# Sheet2.net
KiCad netlist of a schematic drawn in Altium Designer
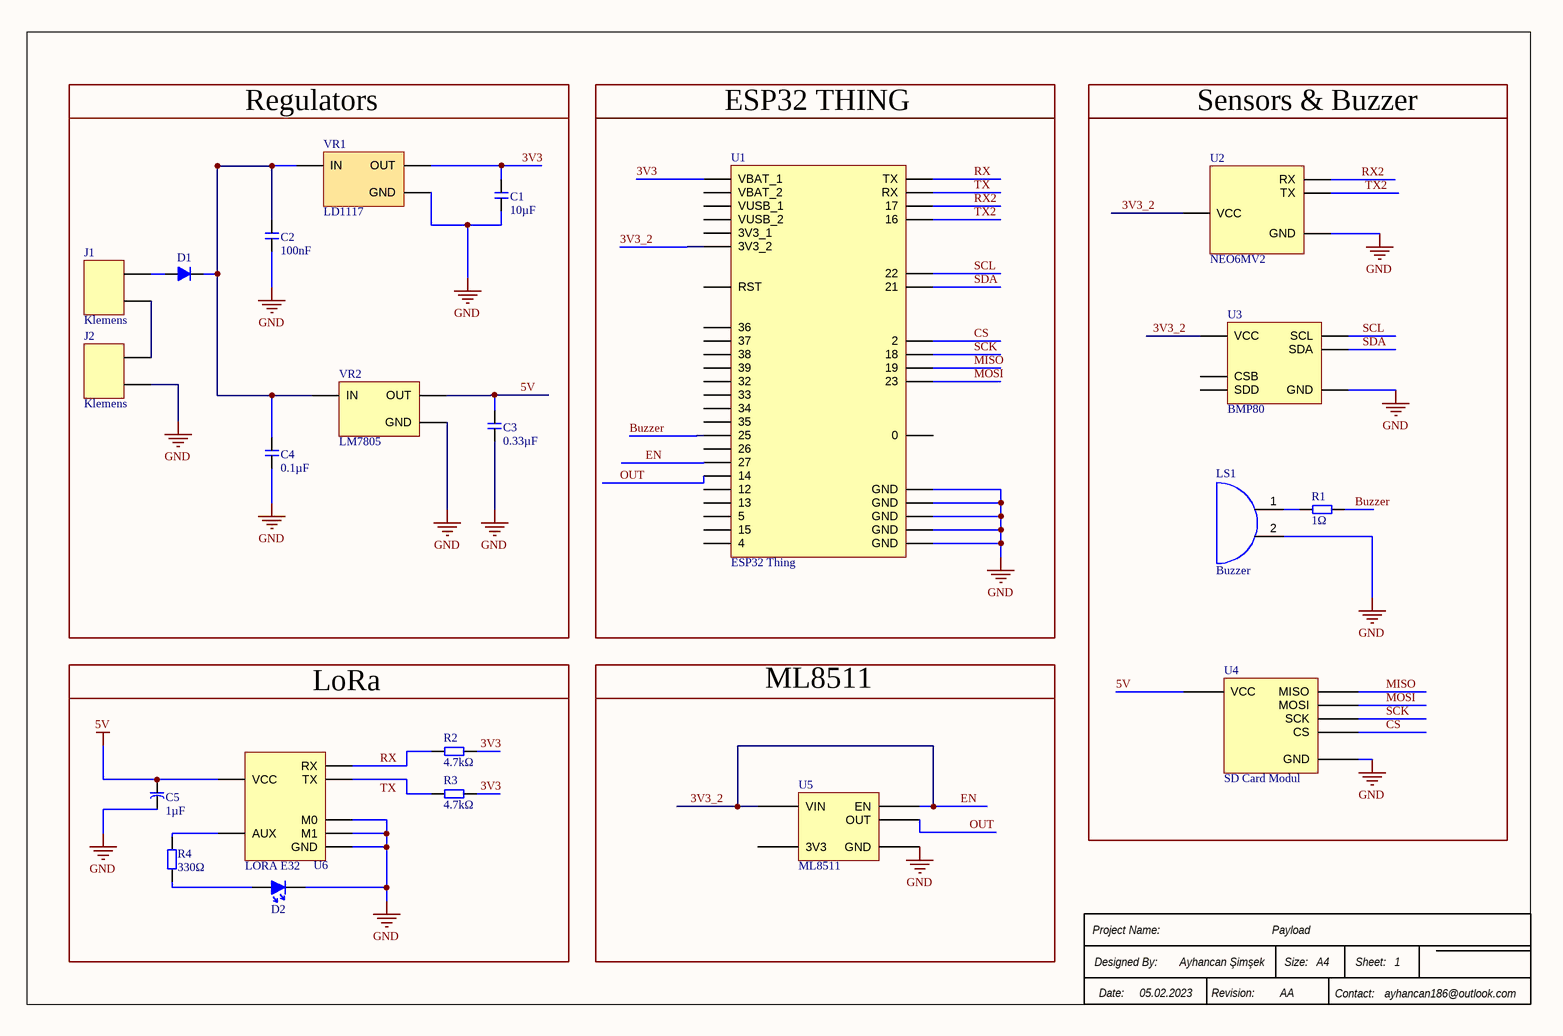
[diagram p0: Sheet2.SchDoc]

(export (version "E")
  (design (tool "Eeschema 10.0.6"))
  (components
    (comp (ref "C1") (value "10µF") (footprint "LCapacitor") (libsource (lib "Schlib1") (part "Capacitor")))
    (comp (ref "C2") (value "100nF") (footprint "LCapacitor") (libsource (lib "Schlib1") (part "Capacitor")))
    (comp (ref "C3") (value "0.33µF") (footprint "LCapacitor") (libsource (lib "Schlib1") (part "Capacitor")))
    (comp (ref "C4") (value "0.1µF") (footprint "LCapacitor") (libsource (lib "Schlib1") (part "Capacitor")))
    (comp (ref "C5") (value "1µF") (footprint "Capacitor") (libsource (lib "Schlib1") (part "DCapacitor")))
    (comp (ref "D1")
      (value "Diode")
      (footprint "Zener")
      (libsource (lib "Integrated_Library2") (part "Diode"))
    )
    (comp (ref "D2") (value "Led") (footprint "LED") (libsource (lib "Integrated_Library2") (part "Led")))
    (comp (ref "J1")
      (value "Klemens")
      (footprint "Klemens")
      (libsource (lib "Integrated_Library2") (part "Klemens"))
    )
    (comp (ref "J2")
      (value "Klemens")
      (footprint "Klemens")
      (libsource (lib "Integrated_Library2") (part "Klemens"))
    )
    (comp (ref "LS1")
      (value "Buzzer")
      (footprint "Buzzer")
      (libsource (lib "Integrated_Library2") (part "Buzzer"))
    )
    (comp (ref "R1") (value "1Ω") (footprint "Resistor") (libsource (lib "Schlib1") (part "Resistor")))
    (comp (ref "R2") (value "4.7kΩ") (footprint "Resistor") (libsource (lib "Schlib1") (part "Resistor")))
    (comp (ref "R3") (value "4.7kΩ") (footprint "Resistor") (libsource (lib "Schlib1") (part "Resistor")))
    (comp (ref "R4") (value "330Ω") (footprint "Resistor") (libsource (lib "Schlib1") (part "Resistor")))
    (comp (ref "U1")
      (value "ESP32 Thing")
      (footprint "ESP32 THING")
      (description "ESP32 802.11 Wireless LAN/Combo Wireless Module Development Kit")
      (fields (field (name "MANUFACTURER") "SparkFun") (field (name "MANUFACTURER PART NUMBER") "DEV-13907"))
      (libsource (lib "Integrated_Library2") (part "ESP32 Thing"))
    )
    (comp (ref "U2")
      (value "NEO6MV2")
      (footprint "NEO6MV2")
      (description "U#NEO-6M Gps Module U-BLOX6 SMD24P")
      (fields (field (name "MANUFACTURER") "u-blox") (field (name "MANUFACTURER PART NUMBER") "NEO-6M-0"))
      (libsource (lib "Integrated_Library2") (part "NEO6MV2"))
    )
    (comp (ref "U3")
      (value "BMP80")
      (footprint "BMP280")
      (description "Washer; #2 Screw Clr; 3/32 ID; 1/4 OD; 1/32 Height; Nylon")
      (fields (field (name "MANUFACTURER") "Bosch") (field (name "MANUFACTURER PART NUMBER") "BMP280"))
      (libsource (lib "Integrated_Library2") (part "BMP80"))
    )
    (comp (ref "U4")
      (value "SD Card Modul")
      (footprint "SD Card Modülü")
      (libsource (lib "Integrated_Library2") (part "SD Card Modul"))
    )
    (comp (ref "U5")
      (value "ML8511")
      (footprint "ML8511")
      (description "IC, Uv Sensor, Voltage Output, QFN-12")
      (fields
        (field (name "MANUFACTURER") "Rohm")
        (field (name "MANUFACTURER PART NUMBER") "ML8511-00FCZ05B")
      )
      (libsource (lib "Integrated_Library2") (part "ML8511"))
    )
    (comp (ref "U6")
      (value "LORA E32")
      (footprint "LORAE32")
      (description "WiFi-Modul 802.11/BT 2, 4-2, 5GHz 150Mb/s")
      (fields
        (field (name "MANUFACTURER") "Espressif Systems")
        (field (name "MANUFACTURER PART NUMBER") "ESP32-S3-WROOM-1-N16R8")
      )
      (libsource (lib "Integrated_Library2") (part "LORA E32"))
    )
    (comp (ref "VR1")
      (value "LD1117")
      (footprint "LD1117")
      (description "LDO Regulator Pos 3.3V 1.3A 3-Pin(3+Tab) TO-220 Tube (Alt: LD1117V33C)")
      (fields
        (field (name "MANUFACTURER") "STMicroelectronics")
        (field (name "MANUFACTURER PART NUMBER") "LD1117V33C")
      )
      (libsource (lib "Integrated_Library2") (part "LD1117"))
    )
    (comp (ref "VR2")
      (value "LM7805")
      (footprint "LM7805")
      (description "LM78XX Series 5 V Fixed Output 1 A 3-Terminal LDO Voltage Regulator - TO-220")
      (fields
        (field (name "MANUFACTURER") "ON Semiconductor / Fairchild")
        (field (name "MANUFACTURER PART NUMBER") "LM7805CT")
      )
      (libsource (lib "Integrated_Library2") (part "LM7805"))
    )
  )
  (nets
    (net (code "1") (name "/3V3") (class "Default")
      (node (ref "C1") (pin "2") (pinfunction "2_2") (pintype "passive"))
      (node (ref "R2") (pin "2") (pinfunction "2_2") (pintype "passive"))
      (node (ref "R3") (pin "2") (pinfunction "2_2") (pintype "passive"))
      (node (ref "U1") (pin "VBAT_1") (pinfunction "VBAT_1_VBAT_1") (pintype "passive"))
      (node (ref "VR1") (pin "2") (pinfunction "OUT_2") (pintype "passive"))
    )
    (net (code "2") (name "/3V3_2") (class "Default")
      (node (ref "U1") (pin "27") (pinfunction "27_27") (pintype "passive"))
      (node (ref "U1") (pin "3V3_2") (pinfunction "3V3_2_3V3_2") (pintype "passive"))
      (node (ref "U2") (pin "1") (pinfunction "VCC_1") (pintype "passive"))
      (node (ref "U3") (pin "1") (pinfunction "VCC_1") (pintype "passive"))
      (node (ref "U5") (pin "EN") (pinfunction "EN_EN") (pintype "passive"))
      (node (ref "U5") (pin "VIN") (pinfunction "VIN_VIN") (pintype "passive"))
    )
    (net (code "3") (name "/Buzzer") (class "Default")
      (node (ref "R1") (pin "1") (pinfunction "1_1") (pintype "passive"))
      (node (ref "U1") (pin "25") (pinfunction "25_25") (pintype "passive"))
    )
    (net (code "4") (name "/CS") (class "Default")
      (node (ref "U1") (pin "2") (pinfunction "2_2") (pintype "passive"))
      (node (ref "U4") (pin "4") (pinfunction "CS_4") (pintype "passive"))
    )
    (net (code "5") (name "/MISO") (class "Default")
      (node (ref "U1") (pin "19") (pinfunction "19_19") (pintype "passive"))
      (node (ref "U4") (pin "3") (pinfunction "MISO_3") (pintype "passive"))
    )
    (net (code "6") (name "/MOSI") (class "Default")
      (node (ref "U1") (pin "23") (pinfunction "23_23") (pintype "passive"))
      (node (ref "U4") (pin "2") (pinfunction "MOSI_2") (pintype "passive"))
    )
    (net (code "7") (name "/OUT") (class "Default")
      (node (ref "U1") (pin "14") (pinfunction "14_14") (pintype "passive"))
      (node (ref "U5") (pin "OUT") (pinfunction "OUT_OUT") (pintype "passive"))
    )
    (net (code "8") (name "/RX") (class "Default")
      (node (ref "R2") (pin "1") (pinfunction "1_1") (pintype "passive"))
      (node (ref "U1") (pin "TX") (pinfunction "TX_TX") (pintype "passive"))
      (node (ref "U6") (pin "5") (pinfunction "RX_5") (pintype "passive"))
    )
    (net (code "9") (name "/RX2") (class "Default")
      (node (ref "U1") (pin "17") (pinfunction "17_17") (pintype "passive"))
      (node (ref "U2") (pin "2") (pinfunction "RX_2") (pintype "passive"))
    )
    (net (code "10") (name "/SCK") (class "Default")
      (node (ref "U1") (pin "18") (pinfunction "18_18") (pintype "passive"))
      (node (ref "U4") (pin "1") (pinfunction "SCK_1") (pintype "passive"))
    )
    (net (code "11") (name "/SCL") (class "Default")
      (node (ref "U1") (pin "22") (pinfunction "22_22") (pintype "passive"))
      (node (ref "U3") (pin "3") (pinfunction "SCL_3") (pintype "passive"))
    )
    (net (code "12") (name "/SDA") (class "Default")
      (node (ref "U1") (pin "21") (pinfunction "21_21") (pintype "passive"))
      (node (ref "U3") (pin "4") (pinfunction "SDA_4") (pintype "passive"))
    )
    (net (code "13") (name "/TX") (class "Default")
      (node (ref "R3") (pin "1") (pinfunction "1_1") (pintype "passive"))
      (node (ref "U1") (pin "RX") (pinfunction "RX_RX") (pintype "passive"))
      (node (ref "U6") (pin "4") (pinfunction "TX_4") (pintype "passive"))
    )
    (net (code "14") (name "/TX2") (class "Default")
      (node (ref "U1") (pin "16") (pinfunction "16_16") (pintype "passive"))
      (node (ref "U2") (pin "3") (pinfunction "TX_3") (pintype "passive"))
    )
    (net (code "15") (name "5V") (class "Default")
      (node (ref "C3") (pin "2") (pinfunction "2_2") (pintype "passive"))
      (node (ref "C5") (pin "1") (pinfunction "1_1") (pintype "passive"))
      (node (ref "U4") (pin "0") (pinfunction "VCC_0") (pintype "passive"))
      (node (ref "U6") (pin "2") (pinfunction "VCC_2") (pintype "passive"))
      (node (ref "VR2") (pin "3") (pinfunction "OUT_3") (pintype "passive"))
    )
    (net (code "16") (name "GND") (class "Default")
      (node (ref "C1") (pin "1") (pinfunction "1_1") (pintype "passive"))
      (node (ref "C2") (pin "1") (pinfunction "1_1") (pintype "passive"))
      (node (ref "C3") (pin "1") (pinfunction "1_1") (pintype "passive"))
      (node (ref "C4") (pin "1") (pinfunction "1_1") (pintype "passive"))
      (node (ref "C5") (pin "2") (pinfunction "2_2") (pintype "passive"))
      (node (ref "D2") (pin "1") (pinfunction "1_1") (pintype "power_in"))
      (node (ref "J2") (pin "1") (pinfunction "1_1") (pintype "passive"))
      (node (ref "LS1") (pin "2") (pinfunction "2_2") (pintype "passive"))
      (node (ref "U1") (pin "GND_1") (pinfunction "GND_GND_1") (pintype "passive"))
      (node (ref "U1") (pin "GND_2") (pinfunction "GND_GND_2") (pintype "passive"))
      (node (ref "U1") (pin "GND_3") (pinfunction "GND_GND_3") (pintype "passive"))
      (node (ref "U1") (pin "GND_4") (pinfunction "GND_GND_4") (pintype "passive"))
      (node (ref "U1") (pin "GND_5") (pinfunction "GND_GND_5") (pintype "passive"))
      (node (ref "U2") (pin "4") (pinfunction "GND_4") (pintype "passive"))
      (node (ref "U3") (pin "2") (pinfunction "GND_2") (pintype "passive"))
      (node (ref "U4") (pin "5") (pinfunction "GND_5") (pintype "passive"))
      (node (ref "U5") (pin "GND") (pinfunction "GND_GND") (pintype "passive"))
      (node (ref "U6") (pin "1") (pinfunction "GND_1") (pintype "passive"))
      (node (ref "U6") (pin "6") (pinfunction "M1_6") (pintype "passive"))
      (node (ref "U6") (pin "7") (pinfunction "M0_7") (pintype "passive"))
      (node (ref "VR1") (pin "3") (pinfunction "GND_3") (pintype "passive"))
      (node (ref "VR2") (pin "2") (pinfunction "GND_2") (pintype "passive"))
    )
    (net (code "17") (name "Net-(D1-Pad1)") (class "Default")
      (node (ref "D1") (pin "1") (pinfunction "1_1") (pintype "passive"))
      (node (ref "J1") (pin "0") (pinfunction "0_0") (pintype "passive"))
    )
    (net (code "18") (name "Net-(D2-Pad2)") (class "Default")
      (node (ref "D2") (pin "2") (pinfunction "2_2") (pintype "power_in"))
      (node (ref "R4") (pin "1") (pinfunction "1_1") (pintype "passive"))
    )
    (net (code "19") (name "Net-(J1-Pad1)") (class "Default")
      (node (ref "J1") (pin "1") (pinfunction "1_1") (pintype "passive"))
      (node (ref "J2") (pin "0") (pinfunction "0_0") (pintype "passive"))
    )
    (net (code "20") (name "Net-(LS1-Pad1)") (class "Default")
      (node (ref "LS1") (pin "1") (pinfunction "1_1") (pintype "passive"))
      (node (ref "R1") (pin "2") (pinfunction "2_2") (pintype "passive"))
    )
    (net (code "21") (name "Net-(U6-AUX)") (class "Default")
      (node (ref "R4") (pin "2") (pinfunction "2_2") (pintype "passive"))
      (node (ref "U6") (pin "3") (pinfunction "AUX_3") (pintype "passive"))
    )
    (net (code "22") (name "Net-(VR1-IN)") (class "Default")
      (node (ref "C2") (pin "2") (pinfunction "2_2") (pintype "passive"))
      (node (ref "C4") (pin "2") (pinfunction "2_2") (pintype "passive"))
      (node (ref "D1") (pin "2") (pinfunction "2_2") (pintype "passive"))
      (node (ref "VR1") (pin "1") (pinfunction "IN_1") (pintype "passive"))
      (node (ref "VR2") (pin "1") (pinfunction "IN_1") (pintype "passive"))
    )
    (net (code "23") (name "unconnected-(U1-Pad0)") (class "Default")
      (node (ref "U1") (pin "0") (pinfunction "0_0") (pintype "passive"))
    )
    (net (code "24") (name "unconnected-(U1-Pad3V3_1)") (class "Default")
      (node (ref "U1") (pin "3V3_1") (pinfunction "3V3_1_3V3_1") (pintype "passive"))
    )
    (net (code "25") (name "unconnected-(U1-Pad4)") (class "Default")
      (node (ref "U1") (pin "4") (pinfunction "4_4") (pintype "passive"))
    )
    (net (code "26") (name "unconnected-(U1-Pad5)") (class "Default")
      (node (ref "U1") (pin "5") (pinfunction "5_5") (pintype "passive"))
    )
    (net (code "27") (name "unconnected-(U1-Pad12)") (class "Default")
      (node (ref "U1") (pin "12") (pinfunction "12_12") (pintype "passive"))
    )
    (net (code "28") (name "unconnected-(U1-Pad13)") (class "Default")
      (node (ref "U1") (pin "13") (pinfunction "13_13") (pintype "passive"))
    )
    (net (code "29") (name "unconnected-(U1-Pad15)") (class "Default")
      (node (ref "U1") (pin "15") (pinfunction "15_15") (pintype "passive"))
    )
    (net (code "30") (name "unconnected-(U1-Pad26)") (class "Default")
      (node (ref "U1") (pin "26") (pinfunction "26_26") (pintype "passive"))
    )
    (net (code "31") (name "unconnected-(U1-Pad32)") (class "Default")
      (node (ref "U1") (pin "32") (pinfunction "32_32") (pintype "passive"))
    )
    (net (code "32") (name "unconnected-(U1-Pad33)") (class "Default")
      (node (ref "U1") (pin "33") (pinfunction "33_33") (pintype "passive"))
    )
    (net (code "33") (name "unconnected-(U1-Pad34)") (class "Default")
      (node (ref "U1") (pin "34") (pinfunction "34_34") (pintype "passive"))
    )
    (net (code "34") (name "unconnected-(U1-Pad35)") (class "Default")
      (node (ref "U1") (pin "35") (pinfunction "35_35") (pintype "passive"))
    )
    (net (code "35") (name "unconnected-(U1-Pad36)") (class "Default")
      (node (ref "U1") (pin "36") (pinfunction "36_36") (pintype "passive"))
    )
    (net (code "36") (name "unconnected-(U1-Pad37)") (class "Default")
      (node (ref "U1") (pin "37") (pinfunction "37_37") (pintype "passive"))
    )
    (net (code "37") (name "unconnected-(U1-Pad38)") (class "Default")
      (node (ref "U1") (pin "38") (pinfunction "38_38") (pintype "passive"))
    )
    (net (code "38") (name "unconnected-(U1-Pad39)") (class "Default")
      (node (ref "U1") (pin "39") (pinfunction "39_39") (pintype "passive"))
    )
    (net (code "39") (name "unconnected-(U1-PadRST)") (class "Default")
      (node (ref "U1") (pin "RST") (pinfunction "RST_RST") (pintype "passive"))
    )
    (net (code "40") (name "unconnected-(U1-PadVBAT_2)") (class "Default")
      (node (ref "U1") (pin "VBAT_2") (pinfunction "VBAT_2_VBAT_2") (pintype "passive"))
    )
    (net (code "41") (name "unconnected-(U1-PadVUSB_1)") (class "Default")
      (node (ref "U1") (pin "VUSB_1") (pinfunction "VUSB_1_VUSB_1") (pintype "passive"))
    )
    (net (code "42") (name "unconnected-(U1-PadVUSB_2)") (class "Default")
      (node (ref "U1") (pin "VUSB_2") (pinfunction "VUSB_2_VUSB_2") (pintype "passive"))
    )
    (net (code "43") (name "unconnected-(U3-CSB-Pad5)") (class "Default")
      (node (ref "U3") (pin "5") (pinfunction "CSB_5") (pintype "passive"))
    )
    (net (code "44") (name "unconnected-(U3-SDD-Pad6)") (class "Default")
      (node (ref "U3") (pin "6") (pinfunction "SDD_6") (pintype "passive"))
    )
    (net (code "45") (name "unconnected-(U5-Pad3V3)") (class "Default")
      (node (ref "U5") (pin "3V3") (pinfunction "3V3_3V3") (pintype "passive"))
    )
  )
)
